# Detect-frelon_TONE3-1.net
KiCad netlist of a schematic drawn in EAGLE
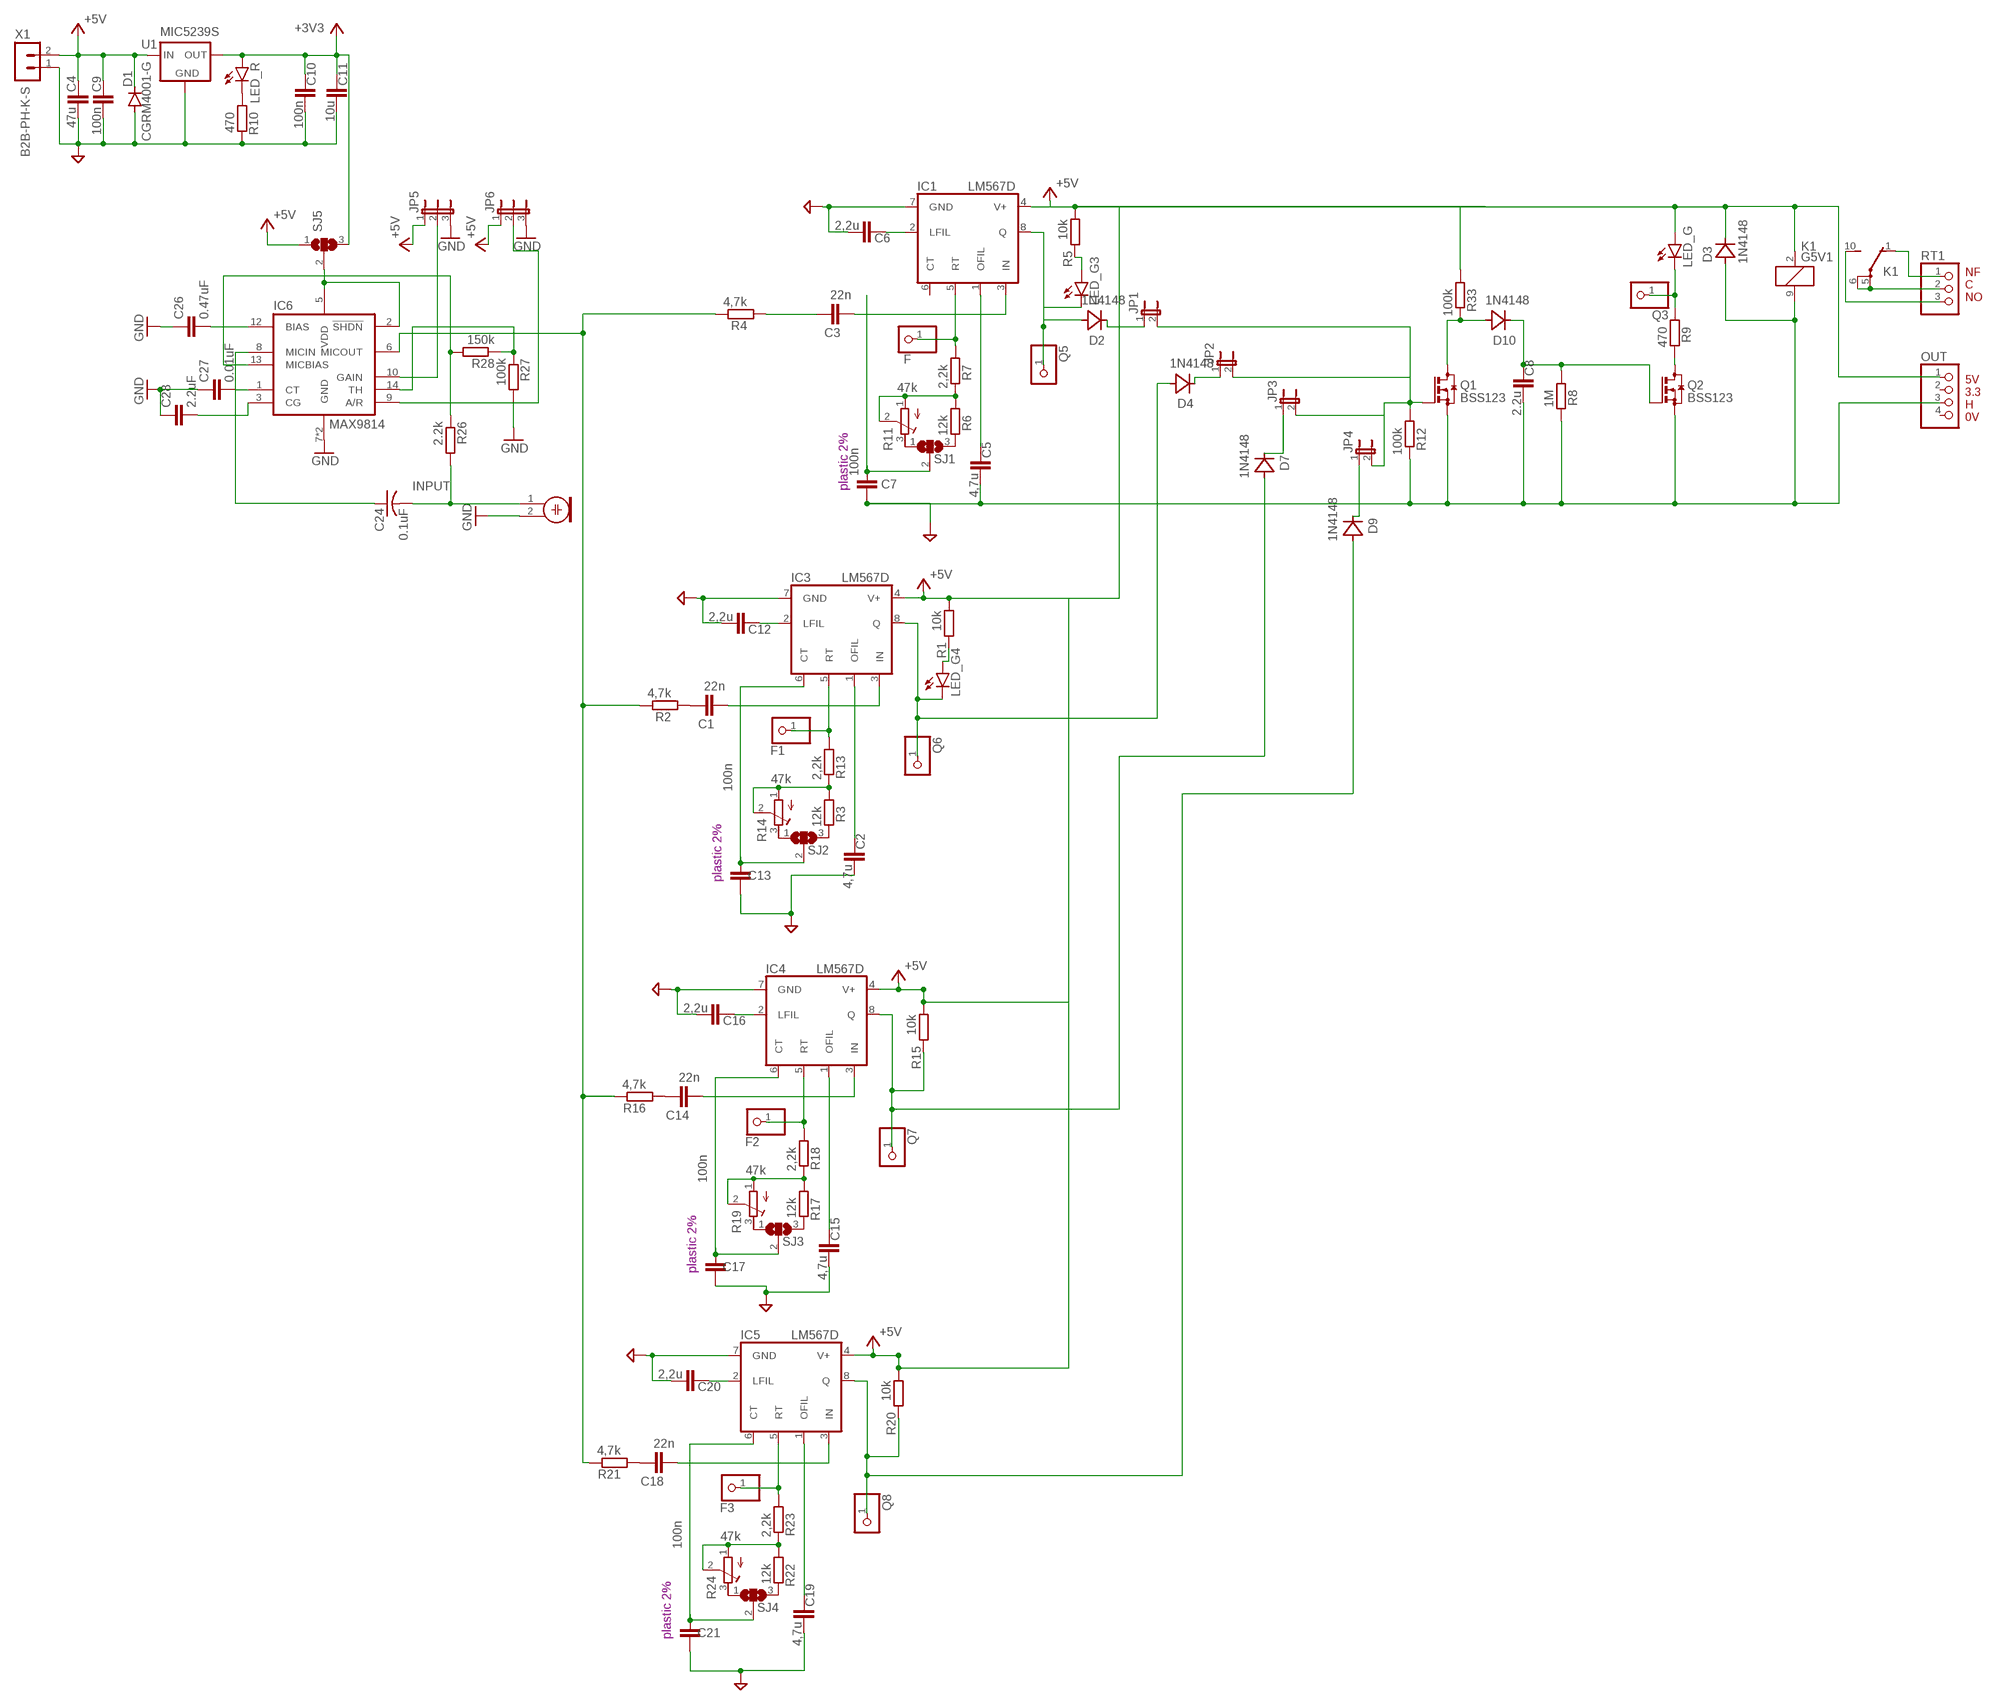
[diagram p0: schematic, sheet 1]

(export (version "E")
  (design (tool "Eeschema 10.0.6"))
  (components
    (comp (ref "C1")
      (value "22n")
      (footprint "eagle-import:C1206")
      (libsource (lib "eagle-import") (part "CC1206"))
    )
    (comp (ref "C2")
      (value "4,7u")
      (footprint "eagle-import:C1206")
      (libsource (lib "eagle-import") (part "CC1206"))
    )
    (comp (ref "C3")
      (value "22n")
      (footprint "eagle-import:C1206")
      (libsource (lib "eagle-import") (part "CC1206"))
    )
    (comp (ref "C4")
      (value "47u")
      (footprint "eagle-import:C1210")
      (libsource (lib "eagle-import") (part "CC1210"))
    )
    (comp (ref "C5")
      (value "4,7u")
      (footprint "eagle-import:C1206")
      (libsource (lib "eagle-import") (part "CC1206"))
    )
    (comp (ref "C6")
      (value "2,2u")
      (footprint "eagle-import:C1206")
      (libsource (lib "eagle-import") (part "CC1206"))
    )
    (comp (ref "C7")
      (value "100n")
      (footprint "eagle-import:C1210")
      (libsource (lib "eagle-import") (part "CC1210"))
    )
    (comp (ref "C8")
      (value "2.2u")
      (footprint "eagle-import:C1210")
      (libsource (lib "eagle-import") (part "CC1210"))
    )
    (comp (ref "C9")
      (value "100n")
      (footprint "eagle-import:C1206")
      (libsource (lib "eagle-import") (part "CC1206"))
    )
    (comp (ref "C10")
      (value "100n")
      (footprint "eagle-import:C1206")
      (libsource (lib "eagle-import") (part "CC1206"))
    )
    (comp (ref "C11")
      (value "10u")
      (footprint "eagle-import:C1210")
      (libsource (lib "eagle-import") (part "CC1210"))
    )
    (comp (ref "C12")
      (value "2,2u")
      (footprint "eagle-import:C1206")
      (libsource (lib "eagle-import") (part "CC1206"))
    )
    (comp (ref "C13")
      (value "100n")
      (footprint "eagle-import:C1210")
      (libsource (lib "eagle-import") (part "CC1210"))
    )
    (comp (ref "C14")
      (value "22n")
      (footprint "eagle-import:C1206")
      (libsource (lib "eagle-import") (part "CC1206"))
    )
    (comp (ref "C15")
      (value "4,7u")
      (footprint "eagle-import:C1206")
      (libsource (lib "eagle-import") (part "CC1206"))
    )
    (comp (ref "C16")
      (value "2,2u")
      (footprint "eagle-import:C1206")
      (libsource (lib "eagle-import") (part "CC1206"))
    )
    (comp (ref "C17")
      (value "100n")
      (footprint "eagle-import:C1210")
      (libsource (lib "eagle-import") (part "CC1210"))
    )
    (comp (ref "C18")
      (value "22n")
      (footprint "eagle-import:C1206")
      (libsource (lib "eagle-import") (part "CC1206"))
    )
    (comp (ref "C19")
      (value "4,7u")
      (footprint "eagle-import:C1206")
      (libsource (lib "eagle-import") (part "CC1206"))
    )
    (comp (ref "C20")
      (value "2,2u")
      (footprint "eagle-import:C1206")
      (libsource (lib "eagle-import") (part "CC1206"))
    )
    (comp (ref "C21")
      (value "100n")
      (footprint "eagle-import:C1210")
      (libsource (lib "eagle-import") (part "CC1210"))
    )
    (comp (ref "C24")
      (value "0.1uF")
      (footprint "eagle-import:C0805K")
      (libsource (lib "eagle-import") (part "C-USC0805K"))
    )
    (comp (ref "C26")
      (value "0.47uF")
      (footprint "eagle-import:C1206")
      (libsource (lib "eagle-import") (part "C-EUC1206"))
    )
    (comp (ref "C27")
      (value "0.01uF")
      (footprint "eagle-import:C1206")
      (libsource (lib "eagle-import") (part "C-EUC1206"))
    )
    (comp (ref "C28")
      (value "2.2uF")
      (footprint "eagle-import:C1206")
      (libsource (lib "eagle-import") (part "C-EUC1206"))
    )
    (comp (ref "D1")
      (value "CGRM4001-G")
      (footprint "eagle-import:SOD-123_MINI-SMA")
      (libsource (lib "eagle-import") (part "CGRM400-G1"))
    )
    (comp (ref "D2")
      (value "1N4148")
      (footprint "eagle-import:VISHAY_1N4148W-E3-08_0")
      (libsource (lib "eagle-import") (part "1N4148"))
    )
    (comp (ref "D3")
      (value "1N4148")
      (footprint "eagle-import:VISHAY_1N4148W-E3-08_0")
      (libsource (lib "eagle-import") (part "1N4148"))
    )
    (comp (ref "D4")
      (value "1N4148")
      (footprint "eagle-import:VISHAY_1N4148W-E3-08_0")
      (libsource (lib "eagle-import") (part "1N4148"))
    )
    (comp (ref "D7")
      (value "1N4148")
      (footprint "eagle-import:VISHAY_1N4148W-E3-08_0")
      (libsource (lib "eagle-import") (part "1N4148"))
    )
    (comp (ref "D9")
      (value "1N4148")
      (footprint "eagle-import:VISHAY_1N4148W-E3-08_0")
      (libsource (lib "eagle-import") (part "1N4148"))
    )
    (comp (ref "D10")
      (value "1N4148")
      (footprint "eagle-import:VISHAY_1N4148W-E3-08_0")
      (libsource (lib "eagle-import") (part "1N4148"))
    )
    (comp (ref "F")
      (value "PINHD-1X1")
      (footprint "eagle-import:1X01")
      (libsource (lib "eagle-import") (part "PINHD-1X1"))
    )
    (comp (ref "F1")
      (value "PINHD-1X1")
      (footprint "eagle-import:1X01")
      (libsource (lib "eagle-import") (part "PINHD-1X1"))
    )
    (comp (ref "F2")
      (value "PINHD-1X1")
      (footprint "eagle-import:1X01")
      (libsource (lib "eagle-import") (part "PINHD-1X1"))
    )
    (comp (ref "F3")
      (value "PINHD-1X1")
      (footprint "eagle-import:1X01")
      (libsource (lib "eagle-import") (part "PINHD-1X1"))
    )
    (comp (ref "IC1")
      (value "LM567D")
      (footprint "eagle-import:SO08")
      (libsource (lib "eagle-import") (part "567DLM"))
    )
    (comp (ref "IC3")
      (value "LM567D")
      (footprint "eagle-import:SO08")
      (libsource (lib "eagle-import") (part "567DLM"))
    )
    (comp (ref "IC4")
      (value "LM567D")
      (footprint "eagle-import:SO08")
      (libsource (lib "eagle-import") (part "567DLM"))
    )
    (comp (ref "IC5")
      (value "LM567D")
      (footprint "eagle-import:SO08")
      (libsource (lib "eagle-import") (part "567DLM"))
    )
    (comp (ref "IC6")
      (value "MAX9814")
      (footprint "eagle-import:TDFN14-EP")
      (libsource (lib "eagle-import") (part "MAX9814"))
    )
    (comp (ref "JP1")
      (value "JP1E")
      (footprint "eagle-import:JP1")
      (libsource (lib "eagle-import") (part "JP1E"))
    )
    (comp (ref "JP2")
      (value "JP1E")
      (footprint "eagle-import:JP1")
      (libsource (lib "eagle-import") (part "JP1E"))
    )
    (comp (ref "JP3")
      (value "JP1E")
      (footprint "eagle-import:JP1")
      (libsource (lib "eagle-import") (part "JP1E"))
    )
    (comp (ref "JP4")
      (value "JP1E")
      (footprint "eagle-import:JP1")
      (libsource (lib "eagle-import") (part "JP1E"))
    )
    (comp (ref "JP5")
      (value "JP2E")
      (footprint "eagle-import:JP2")
      (libsource (lib "eagle-import") (part "JP2E"))
    )
    (comp (ref "JP6")
      (value "JP2E")
      (footprint "eagle-import:JP2")
      (libsource (lib "eagle-import") (part "JP2E"))
    )
    (comp (ref "K1")
      (value "G5V1")
      (footprint "eagle-import:G5V1")
      (fields (field (name "MPN") "G5V-1-DC24"))
      (libsource (lib "eagle-import") (part "G5V1"))
    )
    (comp (ref "LED_G")
      (value "LEDSMT1206")
      (footprint "eagle-import:1206")
      (libsource (lib "eagle-import") (part "LEDSMT1206"))
    )
    (comp (ref "LED_G3")
      (value "LEDSMT1206")
      (footprint "eagle-import:1206")
      (libsource (lib "eagle-import") (part "LEDSMT1206"))
    )
    (comp (ref "LED_G4")
      (value "LEDSMT1206")
      (footprint "eagle-import:1206")
      (libsource (lib "eagle-import") (part "LEDSMT1206"))
    )
    (comp (ref "LED_R")
      (value "LEDSMT1206")
      (footprint "eagle-import:1206")
      (libsource (lib "eagle-import") (part "LEDSMT1206"))
    )
    (comp (ref "M2")
      (value "ELECTRET_MICROPHON-WM-62PC/62PK")
      (footprint "eagle-import:WM-62PC_62PK")
      (libsource (lib "eagle-import") (part "ELECTRET_MICROPHON-WM-62PC/62PK"))
    )
    (comp (ref "OUT")
      (value "PINHD-1X4")
      (footprint "eagle-import:1X04")
      (libsource (lib "eagle-import") (part "PINHD-1X4"))
    )
    (comp (ref "Q1")
      (value "BSS123")
      (footprint "eagle-import:SOT23")
      (libsource (lib "eagle-import") (part "BSS123"))
    )
    (comp (ref "Q2")
      (value "BSS123")
      (footprint "eagle-import:SOT23")
      (libsource (lib "eagle-import") (part "BSS123"))
    )
    (comp (ref "Q3")
      (value "PINHD-1X1")
      (footprint "eagle-import:1X01")
      (libsource (lib "eagle-import") (part "PINHD-1X1"))
    )
    (comp (ref "Q5")
      (value "PINHD-1X1")
      (footprint "eagle-import:1X01")
      (libsource (lib "eagle-import") (part "PINHD-1X1"))
    )
    (comp (ref "Q6")
      (value "PINHD-1X1")
      (footprint "eagle-import:1X01")
      (libsource (lib "eagle-import") (part "PINHD-1X1"))
    )
    (comp (ref "Q7")
      (value "PINHD-1X1")
      (footprint "eagle-import:1X01")
      (libsource (lib "eagle-import") (part "PINHD-1X1"))
    )
    (comp (ref "Q8")
      (value "PINHD-1X1")
      (footprint "eagle-import:1X01")
      (libsource (lib "eagle-import") (part "PINHD-1X1"))
    )
    (comp (ref "R1")
      (value "10k")
      (footprint "eagle-import:R1206")
      (libsource (lib "eagle-import") (part "RR1206"))
    )
    (comp (ref "R2")
      (value "4,7k")
      (footprint "eagle-import:R1206")
      (libsource (lib "eagle-import") (part "RR1206"))
    )
    (comp (ref "R3")
      (value "12k")
      (footprint "eagle-import:R1206")
      (libsource (lib "eagle-import") (part "RR1206"))
    )
    (comp (ref "R4")
      (value "4,7k")
      (footprint "eagle-import:R1206")
      (libsource (lib "eagle-import") (part "RR1206"))
    )
    (comp (ref "R5")
      (value "10k")
      (footprint "eagle-import:R1206")
      (libsource (lib "eagle-import") (part "RR1206"))
    )
    (comp (ref "R6")
      (value "12k")
      (footprint "eagle-import:R1206")
      (libsource (lib "eagle-import") (part "RR1206"))
    )
    (comp (ref "R7")
      (value "2,2k")
      (footprint "eagle-import:R1206")
      (libsource (lib "eagle-import") (part "RR1206"))
    )
    (comp (ref "R8")
      (value "1M")
      (footprint "eagle-import:R1206")
      (libsource (lib "eagle-import") (part "RR1206"))
    )
    (comp (ref "R9")
      (value "470")
      (footprint "eagle-import:R1206")
      (libsource (lib "eagle-import") (part "RR1206"))
    )
    (comp (ref "R10")
      (value "470")
      (footprint "eagle-import:R1206")
      (libsource (lib "eagle-import") (part "RR1206"))
    )
    (comp (ref "R11")
      (value "47k")
      (footprint "eagle-import:RTRIM3296W")
      (libsource (lib "eagle-import") (part "R-TRIMM3296W"))
    )
    (comp (ref "R12")
      (value "100k")
      (footprint "eagle-import:R1206")
      (libsource (lib "eagle-import") (part "RR1206"))
    )
    (comp (ref "R13")
      (value "2,2k")
      (footprint "eagle-import:R1206")
      (libsource (lib "eagle-import") (part "RR1206"))
    )
    (comp (ref "R14")
      (value "47k")
      (footprint "eagle-import:RTRIM3296W")
      (libsource (lib "eagle-import") (part "R-TRIMM3296W"))
    )
    (comp (ref "R15")
      (value "10k")
      (footprint "eagle-import:R1206")
      (libsource (lib "eagle-import") (part "RR1206"))
    )
    (comp (ref "R16")
      (value "4,7k")
      (footprint "eagle-import:R1206")
      (libsource (lib "eagle-import") (part "RR1206"))
    )
    (comp (ref "R17")
      (value "12k")
      (footprint "eagle-import:R1206")
      (libsource (lib "eagle-import") (part "RR1206"))
    )
    (comp (ref "R18")
      (value "2,2k")
      (footprint "eagle-import:R1206")
      (libsource (lib "eagle-import") (part "RR1206"))
    )
    (comp (ref "R19")
      (value "47k")
      (footprint "eagle-import:RTRIM3296W")
      (libsource (lib "eagle-import") (part "R-TRIMM3296W"))
    )
    (comp (ref "R20")
      (value "10k")
      (footprint "eagle-import:R1206")
      (libsource (lib "eagle-import") (part "RR1206"))
    )
    (comp (ref "R21")
      (value "4,7k")
      (footprint "eagle-import:R1206")
      (libsource (lib "eagle-import") (part "RR1206"))
    )
    (comp (ref "R22")
      (value "12k")
      (footprint "eagle-import:R1206")
      (libsource (lib "eagle-import") (part "RR1206"))
    )
    (comp (ref "R23")
      (value "2,2k")
      (footprint "eagle-import:R1206")
      (libsource (lib "eagle-import") (part "RR1206"))
    )
    (comp (ref "R24")
      (value "47k")
      (footprint "eagle-import:RTRIM3296W")
      (libsource (lib "eagle-import") (part "R-TRIMM3296W"))
    )
    (comp (ref "R26")
      (value "2.2k")
      (footprint "eagle-import:R1206")
      (libsource (lib "eagle-import") (part "R-EU_R1206"))
    )
    (comp (ref "R27")
      (value "100k")
      (footprint "eagle-import:R1206")
      (libsource (lib "eagle-import") (part "R-EU_R1206"))
    )
    (comp (ref "R28")
      (value "150k")
      (footprint "eagle-import:R1206")
      (libsource (lib "eagle-import") (part "R-EU_R1206"))
    )
    (comp (ref "R33")
      (value "100k")
      (footprint "eagle-import:R1206")
      (libsource (lib "eagle-import") (part "RR1206"))
    )
    (comp (ref "RT1")
      (value "PINHD-1X3")
      (footprint "eagle-import:1X03")
      (libsource (lib "eagle-import") (part "PINHD-1X3"))
    )
    (comp (ref "SJ1")
      (value "SJ2W")
      (footprint "eagle-import:SJ_2")
      (libsource (lib "eagle-import") (part "SJ2W"))
    )
    (comp (ref "SJ2")
      (value "SJ2W")
      (footprint "eagle-import:SJ_2")
      (libsource (lib "eagle-import") (part "SJ2W"))
    )
    (comp (ref "SJ3")
      (value "SJ2W")
      (footprint "eagle-import:SJ_2")
      (libsource (lib "eagle-import") (part "SJ2W"))
    )
    (comp (ref "SJ4")
      (value "SJ2W")
      (footprint "eagle-import:SJ_2")
      (libsource (lib "eagle-import") (part "SJ2W"))
    )
    (comp (ref "SJ5")
      (value "SJ2W")
      (footprint "eagle-import:SJ_2")
      (libsource (lib "eagle-import") (part "SJ2W"))
    )
    (comp (ref "U1")
      (value "MIC5239S")
      (footprint "eagle-import:SOT223")
      (libsource (lib "eagle-import") (part "MIC5239S"))
    )
    (comp (ref "X1")
      (value "B2B-PH-K-S")
      (footprint "eagle-import:B2B-PH-K-S")
      (libsource (lib "eagle-import") (part "B2B-PH-K-S"))
    )
  )
  (nets
    (net (code "1") (name "+3V3") (class "Default")
      (node (ref "C10") (pin "1") (pinfunction "1_1") (pintype "passive"))
      (node (ref "C11") (pin "1") (pinfunction "1_1") (pintype "passive"))
      (node (ref "LED_R") (pin "A") (pinfunction "A_A") (pintype "passive"))
      (node (ref "SJ5") (pin "3") (pinfunction "3_3") (pintype "passive"))
      (node (ref "U1") (pin "3") (pinfunction "OUT_3") (pintype "passive"))
    )
    (net (code "2") (name "+5V") (class "Default")
      (node (ref "C4") (pin "1") (pinfunction "1_1") (pintype "passive"))
      (node (ref "C9") (pin "1") (pinfunction "1_1") (pintype "passive"))
      (node (ref "D1") (pin "C") (pinfunction "C_C") (pintype "passive"))
      (node (ref "D3") (pin "1") (pinfunction "C_1") (pintype "passive"))
      (node (ref "IC1") (pin "4") (pinfunction "V+_4") (pintype "power_in"))
      (node (ref "IC3") (pin "4") (pinfunction "V+_4") (pintype "power_in"))
      (node (ref "IC4") (pin "4") (pinfunction "V+_4") (pintype "power_in"))
      (node (ref "IC5") (pin "4") (pinfunction "V+_4") (pintype "power_in"))
      (node (ref "JP5") (pin "1") (pinfunction "1_1") (pintype "passive"))
      (node (ref "JP6") (pin "1") (pinfunction "1_1") (pintype "passive"))
      (node (ref "K1") (pin "2") (pinfunction "1_2") (pintype "passive"))
      (node (ref "LED_G") (pin "A") (pinfunction "A_A") (pintype "passive"))
      (node (ref "OUT") (pin "1") (pinfunction "1_1") (pintype "passive"))
      (node (ref "R1") (pin "1") (pinfunction "1_1") (pintype "passive"))
      (node (ref "R15") (pin "1") (pinfunction "1_1") (pintype "passive"))
      (node (ref "R20") (pin "1") (pinfunction "1_1") (pintype "passive"))
      (node (ref "R33") (pin "1") (pinfunction "1_1") (pintype "passive"))
      (node (ref "R5") (pin "1") (pinfunction "1_1") (pintype "passive"))
      (node (ref "SJ5") (pin "1") (pinfunction "1_1") (pintype "passive"))
      (node (ref "U1") (pin "1") (pinfunction "IN_1") (pintype "input"))
      (node (ref "X1") (pin "2") (pinfunction "2_2") (pintype "passive"))
    )
    (net (code "3") (name "/INPUT") (class "Default")
      (node (ref "C24") (pin "2") (pinfunction "2_2") (pintype "passive"))
      (node (ref "M2") (pin "1") (pinfunction "1_1") (pintype "passive"))
      (node (ref "R26") (pin "2") (pinfunction "2_2") (pintype "passive"))
    )
    (net (code "4") (name "GND") (class "Default")
      (node (ref "C10") (pin "2") (pinfunction "2_2") (pintype "passive"))
      (node (ref "C11") (pin "2") (pinfunction "2_2") (pintype "passive"))
      (node (ref "C12") (pin "2") (pinfunction "2_2") (pintype "passive"))
      (node (ref "C13") (pin "2") (pinfunction "2_2") (pintype "passive"))
      (node (ref "C15") (pin "2") (pinfunction "2_2") (pintype "passive"))
      (node (ref "C16") (pin "2") (pinfunction "2_2") (pintype "passive"))
      (node (ref "C17") (pin "2") (pinfunction "2_2") (pintype "passive"))
      (node (ref "C19") (pin "2") (pinfunction "2_2") (pintype "passive"))
      (node (ref "C2") (pin "2") (pinfunction "2_2") (pintype "passive"))
      (node (ref "C20") (pin "2") (pinfunction "2_2") (pintype "passive"))
      (node (ref "C21") (pin "2") (pinfunction "2_2") (pintype "passive"))
      (node (ref "C26") (pin "1") (pinfunction "1_1") (pintype "passive"))
      (node (ref "C27") (pin "1") (pinfunction "1_1") (pintype "passive"))
      (node (ref "C28") (pin "1") (pinfunction "1_1") (pintype "passive"))
      (node (ref "C4") (pin "2") (pinfunction "2_2") (pintype "passive"))
      (node (ref "C5") (pin "2") (pinfunction "2_2") (pintype "passive"))
      (node (ref "C6") (pin "2") (pinfunction "2_2") (pintype "passive"))
      (node (ref "C7") (pin "2") (pinfunction "2_2") (pintype "passive"))
      (node (ref "C8") (pin "2") (pinfunction "2_2") (pintype "passive"))
      (node (ref "C9") (pin "2") (pinfunction "2_2") (pintype "passive"))
      (node (ref "D1") (pin "A") (pinfunction "A_A") (pintype "passive"))
      (node (ref "D3") (pin "2") (pinfunction "A_2") (pintype "passive"))
      (node (ref "IC1") (pin "7") (pinfunction "GND_7") (pintype "power_in"))
      (node (ref "IC3") (pin "7") (pinfunction "GND_7") (pintype "power_in"))
      (node (ref "IC4") (pin "7") (pinfunction "GND_7") (pintype "power_in"))
      (node (ref "IC5") (pin "7") (pinfunction "GND_7") (pintype "power_in"))
      (node (ref "IC6") (pin "7") (pinfunction "GND_7") (pintype "power_in"))
      (node (ref "IC6") (pin "EP") (pinfunction "GND_EP") (pintype "power_in"))
      (node (ref "JP5") (pin "3") (pinfunction "3_3") (pintype "passive"))
      (node (ref "JP6") (pin "3") (pinfunction "3_3") (pintype "passive"))
      (node (ref "K1") (pin "9") (pinfunction "2_9") (pintype "passive"))
      (node (ref "M2") (pin "2") (pinfunction "2_2") (pintype "passive"))
      (node (ref "OUT") (pin "3") (pinfunction "3_3") (pintype "passive"))
      (node (ref "Q1") (pin "2") (pinfunction "S_2") (pintype "passive"))
      (node (ref "Q2") (pin "2") (pinfunction "S_2") (pintype "passive"))
      (node (ref "R10") (pin "2") (pinfunction "2_2") (pintype "passive"))
      (node (ref "R12") (pin "2") (pinfunction "2_2") (pintype "passive"))
      (node (ref "R27") (pin "2") (pinfunction "2_2") (pintype "passive"))
      (node (ref "R8") (pin "2") (pinfunction "2_2") (pintype "passive"))
      (node (ref "U1") (pin "2") (pinfunction "GND_2") (pintype "passive"))
      (node (ref "U1") (pin "4") (pinfunction "GND_4") (pintype "passive"))
      (node (ref "X1") (pin "1") (pinfunction "1_1") (pintype "passive"))
    )
    (net (code "5") (name "Net-(C1-Pad1)") (class "Default")
      (node (ref "C1") (pin "1") (pinfunction "1_1") (pintype "passive"))
      (node (ref "R2") (pin "1") (pinfunction "1_1") (pintype "passive"))
    )
    (net (code "6") (name "Net-(C3-Pad1)") (class "Default")
      (node (ref "C3") (pin "1") (pinfunction "1_1") (pintype "passive"))
      (node (ref "R4") (pin "1") (pinfunction "1_1") (pintype "passive"))
    )
    (net (code "7") (name "Net-(C7-Pad1)") (class "Default")
      (node (ref "C7") (pin "1") (pinfunction "1_1") (pintype "passive"))
      (node (ref "SJ1") (pin "2") (pinfunction "2_2") (pintype "passive"))
    )
    (net (code "8") (name "Net-(C14-Pad1)") (class "Default")
      (node (ref "C14") (pin "1") (pinfunction "1_1") (pintype "passive"))
      (node (ref "R16") (pin "1") (pinfunction "1_1") (pintype "passive"))
    )
    (net (code "9") (name "Net-(C18-Pad1)") (class "Default")
      (node (ref "C18") (pin "1") (pinfunction "1_1") (pintype "passive"))
      (node (ref "R21") (pin "1") (pinfunction "1_1") (pintype "passive"))
    )
    (net (code "10") (name "Net-(D2-A)") (class "Default")
      (node (ref "D2") (pin "2") (pinfunction "A_2") (pintype "passive"))
      (node (ref "IC1") (pin "8") (pinfunction "Q_8") (pintype "output"))
      (node (ref "LED_G3") (pin "C") (pinfunction "C_C") (pintype "passive"))
      (node (ref "Q5") (pin "1") (pinfunction "1_1") (pintype "passive"))
    )
    (net (code "11") (name "Net-(D2-C)") (class "Default")
      (node (ref "D2") (pin "1") (pinfunction "C_1") (pintype "passive"))
      (node (ref "JP1") (pin "1") (pinfunction "1_1") (pintype "passive"))
    )
    (net (code "12") (name "Net-(D4-A)") (class "Default")
      (node (ref "D4") (pin "2") (pinfunction "A_2") (pintype "passive"))
      (node (ref "IC3") (pin "8") (pinfunction "Q_8") (pintype "output"))
      (node (ref "LED_G4") (pin "C") (pinfunction "C_C") (pintype "passive"))
      (node (ref "Q6") (pin "1") (pinfunction "1_1") (pintype "passive"))
    )
    (net (code "13") (name "Net-(D4-C)") (class "Default")
      (node (ref "D4") (pin "1") (pinfunction "C_1") (pintype "passive"))
      (node (ref "JP2") (pin "1") (pinfunction "1_1") (pintype "passive"))
    )
    (net (code "14") (name "Net-(D7-A)") (class "Default")
      (node (ref "D7") (pin "2") (pinfunction "A_2") (pintype "passive"))
      (node (ref "IC4") (pin "8") (pinfunction "Q_8") (pintype "output"))
      (node (ref "Q7") (pin "1") (pinfunction "1_1") (pintype "passive"))
      (node (ref "R15") (pin "2") (pinfunction "2_2") (pintype "passive"))
    )
    (net (code "15") (name "Net-(D7-C)") (class "Default")
      (node (ref "D7") (pin "1") (pinfunction "C_1") (pintype "passive"))
      (node (ref "JP3") (pin "1") (pinfunction "1_1") (pintype "passive"))
    )
    (net (code "16") (name "Net-(D9-A)") (class "Default")
      (node (ref "D9") (pin "2") (pinfunction "A_2") (pintype "passive"))
      (node (ref "IC5") (pin "8") (pinfunction "Q_8") (pintype "output"))
      (node (ref "Q8") (pin "1") (pinfunction "1_1") (pintype "passive"))
      (node (ref "R20") (pin "2") (pinfunction "2_2") (pintype "passive"))
    )
    (net (code "17") (name "Net-(D9-C)") (class "Default")
      (node (ref "D9") (pin "1") (pinfunction "C_1") (pintype "passive"))
      (node (ref "JP4") (pin "1") (pinfunction "1_1") (pintype "passive"))
    )
    (net (code "18") (name "Net-(D10-A)") (class "Default")
      (node (ref "D10") (pin "2") (pinfunction "A_2") (pintype "passive"))
      (node (ref "Q1") (pin "3") (pinfunction "D_3") (pintype "passive"))
      (node (ref "R33") (pin "2") (pinfunction "2_2") (pintype "passive"))
    )
    (net (code "19") (name "Net-(D10-C)") (class "Default")
      (node (ref "C8") (pin "1") (pinfunction "1_1") (pintype "passive"))
      (node (ref "D10") (pin "1") (pinfunction "C_1") (pintype "passive"))
      (node (ref "Q2") (pin "1") (pinfunction "G_1") (pintype "passive"))
      (node (ref "R8") (pin "1") (pinfunction "1_1") (pintype "passive"))
    )
    (net (code "20") (name "Net-(IC1-IN)") (class "Default")
      (node (ref "C3") (pin "2") (pinfunction "2_2") (pintype "passive"))
      (node (ref "IC1") (pin "3") (pinfunction "IN_3") (pintype "input"))
    )
    (net (code "21") (name "Net-(IC1-LFIL)") (class "Default")
      (node (ref "C6") (pin "1") (pinfunction "1_1") (pintype "passive"))
      (node (ref "IC1") (pin "2") (pinfunction "LFIL_2") (pintype "passive"))
    )
    (net (code "22") (name "Net-(IC1-OFIL)") (class "Default")
      (node (ref "C5") (pin "1") (pinfunction "1_1") (pintype "passive"))
      (node (ref "IC1") (pin "1") (pinfunction "OFIL_1") (pintype "output"))
    )
    (net (code "23") (name "Net-(IC1-RT)") (class "Default")
      (node (ref "F") (pin "1") (pinfunction "1_1") (pintype "passive"))
      (node (ref "IC1") (pin "5") (pinfunction "RT_5") (pintype "passive"))
      (node (ref "R7") (pin "1") (pinfunction "1_1") (pintype "passive"))
    )
    (net (code "24") (name "Net-(IC3-CT)") (class "Default")
      (node (ref "C13") (pin "1") (pinfunction "1_1") (pintype "passive"))
      (node (ref "IC3") (pin "6") (pinfunction "CT_6") (pintype "passive"))
      (node (ref "SJ2") (pin "2") (pinfunction "2_2") (pintype "passive"))
    )
    (net (code "25") (name "Net-(IC3-IN)") (class "Default")
      (node (ref "C1") (pin "2") (pinfunction "2_2") (pintype "passive"))
      (node (ref "IC3") (pin "3") (pinfunction "IN_3") (pintype "input"))
    )
    (net (code "26") (name "Net-(IC3-LFIL)") (class "Default")
      (node (ref "C12") (pin "1") (pinfunction "1_1") (pintype "passive"))
      (node (ref "IC3") (pin "2") (pinfunction "LFIL_2") (pintype "passive"))
    )
    (net (code "27") (name "Net-(IC3-OFIL)") (class "Default")
      (node (ref "C2") (pin "1") (pinfunction "1_1") (pintype "passive"))
      (node (ref "IC3") (pin "1") (pinfunction "OFIL_1") (pintype "output"))
    )
    (net (code "28") (name "Net-(IC3-RT)") (class "Default")
      (node (ref "F1") (pin "1") (pinfunction "1_1") (pintype "passive"))
      (node (ref "IC3") (pin "5") (pinfunction "RT_5") (pintype "passive"))
      (node (ref "R13") (pin "1") (pinfunction "1_1") (pintype "passive"))
    )
    (net (code "29") (name "Net-(IC4-CT)") (class "Default")
      (node (ref "C17") (pin "1") (pinfunction "1_1") (pintype "passive"))
      (node (ref "IC4") (pin "6") (pinfunction "CT_6") (pintype "passive"))
      (node (ref "SJ3") (pin "2") (pinfunction "2_2") (pintype "passive"))
    )
    (net (code "30") (name "Net-(IC4-IN)") (class "Default")
      (node (ref "C14") (pin "2") (pinfunction "2_2") (pintype "passive"))
      (node (ref "IC4") (pin "3") (pinfunction "IN_3") (pintype "input"))
    )
    (net (code "31") (name "Net-(IC4-LFIL)") (class "Default")
      (node (ref "C16") (pin "1") (pinfunction "1_1") (pintype "passive"))
      (node (ref "IC4") (pin "2") (pinfunction "LFIL_2") (pintype "passive"))
    )
    (net (code "32") (name "Net-(IC4-OFIL)") (class "Default")
      (node (ref "C15") (pin "1") (pinfunction "1_1") (pintype "passive"))
      (node (ref "IC4") (pin "1") (pinfunction "OFIL_1") (pintype "output"))
    )
    (net (code "33") (name "Net-(IC4-RT)") (class "Default")
      (node (ref "F2") (pin "1") (pinfunction "1_1") (pintype "passive"))
      (node (ref "IC4") (pin "5") (pinfunction "RT_5") (pintype "passive"))
      (node (ref "R18") (pin "1") (pinfunction "1_1") (pintype "passive"))
    )
    (net (code "34") (name "Net-(IC5-CT)") (class "Default")
      (node (ref "C21") (pin "1") (pinfunction "1_1") (pintype "passive"))
      (node (ref "IC5") (pin "6") (pinfunction "CT_6") (pintype "passive"))
      (node (ref "SJ4") (pin "2") (pinfunction "2_2") (pintype "passive"))
    )
    (net (code "35") (name "Net-(IC5-IN)") (class "Default")
      (node (ref "C18") (pin "2") (pinfunction "2_2") (pintype "passive"))
      (node (ref "IC5") (pin "3") (pinfunction "IN_3") (pintype "input"))
    )
    (net (code "36") (name "Net-(IC5-LFIL)") (class "Default")
      (node (ref "C20") (pin "1") (pinfunction "1_1") (pintype "passive"))
      (node (ref "IC5") (pin "2") (pinfunction "LFIL_2") (pintype "passive"))
    )
    (net (code "37") (name "Net-(IC5-OFIL)") (class "Default")
      (node (ref "C19") (pin "1") (pinfunction "1_1") (pintype "passive"))
      (node (ref "IC5") (pin "1") (pinfunction "OFIL_1") (pintype "output"))
    )
    (net (code "38") (name "Net-(IC5-RT)") (class "Default")
      (node (ref "F3") (pin "1") (pinfunction "1_1") (pintype "passive"))
      (node (ref "IC5") (pin "5") (pinfunction "RT_5") (pintype "passive"))
      (node (ref "R23") (pin "1") (pinfunction "1_1") (pintype "passive"))
    )
    (net (code "39") (name "Net-(IC6-A{slash}R)") (class "Default")
      (node (ref "IC6") (pin "9") (pinfunction "A/R_9") (pintype "input"))
      (node (ref "JP6") (pin "2") (pinfunction "2_2") (pintype "passive"))
    )
    (net (code "40") (name "Net-(IC6-BIAS)") (class "Default")
      (node (ref "C26") (pin "2") (pinfunction "2_2") (pintype "passive"))
      (node (ref "IC6") (pin "12") (pinfunction "BIAS_12") (pintype "input"))
    )
    (net (code "41") (name "Net-(IC6-CG)") (class "Default")
      (node (ref "C28") (pin "2") (pinfunction "2_2") (pintype "passive"))
      (node (ref "IC6") (pin "3") (pinfunction "CG_3") (pintype "input"))
    )
    (net (code "42") (name "Net-(IC6-CT)") (class "Default")
      (node (ref "C27") (pin "2") (pinfunction "2_2") (pintype "passive"))
      (node (ref "IC6") (pin "1") (pinfunction "CT_1") (pintype "input"))
    )
    (net (code "43") (name "Net-(IC6-GAIN)") (class "Default")
      (node (ref "IC6") (pin "10") (pinfunction "GAIN_10") (pintype "input"))
      (node (ref "JP5") (pin "2") (pinfunction "2_2") (pintype "passive"))
    )
    (net (code "44") (name "Net-(IC6-MICBIAS)") (class "Default")
      (node (ref "IC6") (pin "13") (pinfunction "MICBIAS_13") (pintype "output"))
      (node (ref "R26") (pin "1") (pinfunction "1_1") (pintype "passive"))
      (node (ref "R28") (pin "2") (pinfunction "2_2") (pintype "passive"))
    )
    (net (code "45") (name "Net-(IC6-MICIN)") (class "Default")
      (node (ref "C24") (pin "1") (pinfunction "1_1") (pintype "passive"))
      (node (ref "IC6") (pin "8") (pinfunction "MICIN_8") (pintype "input"))
    )
    (net (code "46") (name "Net-(IC6-MICOUT)") (class "Default")
      (node (ref "IC6") (pin "6") (pinfunction "MICOUT_6") (pintype "output"))
      (node (ref "R16") (pin "2") (pinfunction "2_2") (pintype "passive"))
      (node (ref "R2") (pin "2") (pinfunction "2_2") (pintype "passive"))
      (node (ref "R21") (pin "2") (pinfunction "2_2") (pintype "passive"))
      (node (ref "R4") (pin "2") (pinfunction "2_2") (pintype "passive"))
    )
    (net (code "47") (name "Net-(IC6-TH)") (class "Default")
      (node (ref "IC6") (pin "14") (pinfunction "TH_14") (pintype "input"))
      (node (ref "R27") (pin "1") (pinfunction "1_1") (pintype "passive"))
      (node (ref "R28") (pin "1") (pinfunction "1_1") (pintype "passive"))
    )
    (net (code "48") (name "Net-(IC6-VDD)") (class "Default")
      (node (ref "IC6") (pin "2") (pinfunction "~{SHDN}_2") (pintype "input"))
      (node (ref "IC6") (pin "5") (pinfunction "VDD_5") (pintype "power_in"))
      (node (ref "SJ5") (pin "2") (pinfunction "2_2") (pintype "passive"))
    )
    (net (code "49") (name "Net-(K1B-O)") (class "Default")
      (node (ref "K1") (pin "1") (pinfunction "O_1") (pintype "passive"))
      (node (ref "RT1") (pin "1") (pinfunction "1_1") (pintype "passive"))
    )
    (net (code "50") (name "Net-(K1B-P-Pad5)") (class "Default")
      (node (ref "K1") (pin "5") (pinfunction "P_5") (pintype "passive"))
      (node (ref "K1") (pin "6") (pinfunction "P_6") (pintype "passive"))
      (node (ref "RT1") (pin "2") (pinfunction "2_2") (pintype "passive"))
    )
    (net (code "51") (name "Net-(K1B-S)") (class "Default")
      (node (ref "K1") (pin "10") (pinfunction "S_10") (pintype "passive"))
      (node (ref "RT1") (pin "3") (pinfunction "3_3") (pintype "passive"))
    )
    (net (code "52") (name "Net-(LED_G-PadC)") (class "Default")
      (node (ref "LED_G") (pin "C") (pinfunction "C_C") (pintype "passive"))
      (node (ref "Q3") (pin "1") (pinfunction "1_1") (pintype "passive"))
      (node (ref "R9") (pin "1") (pinfunction "1_1") (pintype "passive"))
    )
    (net (code "53") (name "Net-(LED_G3-PadA)") (class "Default")
      (node (ref "LED_G3") (pin "A") (pinfunction "A_A") (pintype "passive"))
      (node (ref "R5") (pin "2") (pinfunction "2_2") (pintype "passive"))
    )
    (net (code "54") (name "Net-(LED_G4-PadA)") (class "Default")
      (node (ref "LED_G4") (pin "A") (pinfunction "A_A") (pintype "passive"))
      (node (ref "R1") (pin "2") (pinfunction "2_2") (pintype "passive"))
    )
    (net (code "55") (name "Net-(LED_R-PadC)") (class "Default")
      (node (ref "LED_R") (pin "C") (pinfunction "C_C") (pintype "passive"))
      (node (ref "R10") (pin "1") (pinfunction "1_1") (pintype "passive"))
    )
    (net (code "56") (name "Net-(Q1-G)") (class "Default")
      (node (ref "JP1") (pin "2") (pinfunction "2_2") (pintype "passive"))
      (node (ref "JP2") (pin "2") (pinfunction "2_2") (pintype "passive"))
      (node (ref "JP3") (pin "2") (pinfunction "2_2") (pintype "passive"))
      (node (ref "JP4") (pin "2") (pinfunction "2_2") (pintype "passive"))
      (node (ref "Q1") (pin "1") (pinfunction "G_1") (pintype "passive"))
      (node (ref "R12") (pin "1") (pinfunction "1_1") (pintype "passive"))
    )
    (net (code "57") (name "Net-(Q2-D)") (class "Default")
      (node (ref "Q2") (pin "3") (pinfunction "D_3") (pintype "passive"))
      (node (ref "R9") (pin "2") (pinfunction "2_2") (pintype "passive"))
    )
    (net (code "58") (name "Net-(R3-Pad2)") (class "Default")
      (node (ref "R3") (pin "2") (pinfunction "2_2") (pintype "passive"))
      (node (ref "SJ2") (pin "3") (pinfunction "3_3") (pintype "passive"))
    )
    (net (code "59") (name "Net-(R6-Pad2)") (class "Default")
      (node (ref "R6") (pin "2") (pinfunction "2_2") (pintype "passive"))
      (node (ref "SJ1") (pin "3") (pinfunction "3_3") (pintype "passive"))
    )
    (net (code "60") (name "Net-(R11-A)") (class "Default")
      (node (ref "R11") (pin "1") (pinfunction "A_1") (pintype "passive"))
      (node (ref "R11") (pin "2") (pinfunction "S_2") (pintype "passive"))
      (node (ref "R6") (pin "1") (pinfunction "1_1") (pintype "passive"))
      (node (ref "R7") (pin "2") (pinfunction "2_2") (pintype "passive"))
    )
    (net (code "61") (name "Net-(R11-E)") (class "Default")
      (node (ref "R11") (pin "3") (pinfunction "E_3") (pintype "passive"))
      (node (ref "SJ1") (pin "1") (pinfunction "1_1") (pintype "passive"))
    )
    (net (code "62") (name "Net-(R14-A)") (class "Default")
      (node (ref "R13") (pin "2") (pinfunction "2_2") (pintype "passive"))
      (node (ref "R14") (pin "1") (pinfunction "A_1") (pintype "passive"))
      (node (ref "R14") (pin "2") (pinfunction "S_2") (pintype "passive"))
      (node (ref "R3") (pin "1") (pinfunction "1_1") (pintype "passive"))
    )
    (net (code "63") (name "Net-(R14-E)") (class "Default")
      (node (ref "R14") (pin "3") (pinfunction "E_3") (pintype "passive"))
      (node (ref "SJ2") (pin "1") (pinfunction "1_1") (pintype "passive"))
    )
    (net (code "64") (name "Net-(R17-Pad2)") (class "Default")
      (node (ref "R17") (pin "2") (pinfunction "2_2") (pintype "passive"))
      (node (ref "SJ3") (pin "3") (pinfunction "3_3") (pintype "passive"))
    )
    (net (code "65") (name "Net-(R19-A)") (class "Default")
      (node (ref "R17") (pin "1") (pinfunction "1_1") (pintype "passive"))
      (node (ref "R18") (pin "2") (pinfunction "2_2") (pintype "passive"))
      (node (ref "R19") (pin "1") (pinfunction "A_1") (pintype "passive"))
      (node (ref "R19") (pin "2") (pinfunction "S_2") (pintype "passive"))
    )
    (net (code "66") (name "Net-(R19-E)") (class "Default")
      (node (ref "R19") (pin "3") (pinfunction "E_3") (pintype "passive"))
      (node (ref "SJ3") (pin "1") (pinfunction "1_1") (pintype "passive"))
    )
    (net (code "67") (name "Net-(R22-Pad2)") (class "Default")
      (node (ref "R22") (pin "2") (pinfunction "2_2") (pintype "passive"))
      (node (ref "SJ4") (pin "3") (pinfunction "3_3") (pintype "passive"))
    )
    (net (code "68") (name "Net-(R24-A)") (class "Default")
      (node (ref "R22") (pin "1") (pinfunction "1_1") (pintype "passive"))
      (node (ref "R23") (pin "2") (pinfunction "2_2") (pintype "passive"))
      (node (ref "R24") (pin "1") (pinfunction "A_1") (pintype "passive"))
      (node (ref "R24") (pin "2") (pinfunction "S_2") (pintype "passive"))
    )
    (net (code "69") (name "Net-(R24-E)") (class "Default")
      (node (ref "R24") (pin "3") (pinfunction "E_3") (pintype "passive"))
      (node (ref "SJ4") (pin "1") (pinfunction "1_1") (pintype "passive"))
    )
    (net (code "70") (name "unconnected-(IC1-CT-Pad6)") (class "Default")
      (node (ref "IC1") (pin "6") (pinfunction "CT_6") (pintype "passive"))
    )
    (net (code "71") (name "unconnected-(OUT-Pad2)") (class "Default")
      (node (ref "OUT") (pin "2") (pinfunction "2_2") (pintype "passive"))
    )
    (net (code "72") (name "unconnected-(OUT-Pad4)") (class "Default")
      (node (ref "OUT") (pin "4") (pinfunction "4_4") (pintype "passive"))
    )
  )
)
